# 06_PFI_Buffer.net
KiCad netlist of a schematic drawn in Altium Designer
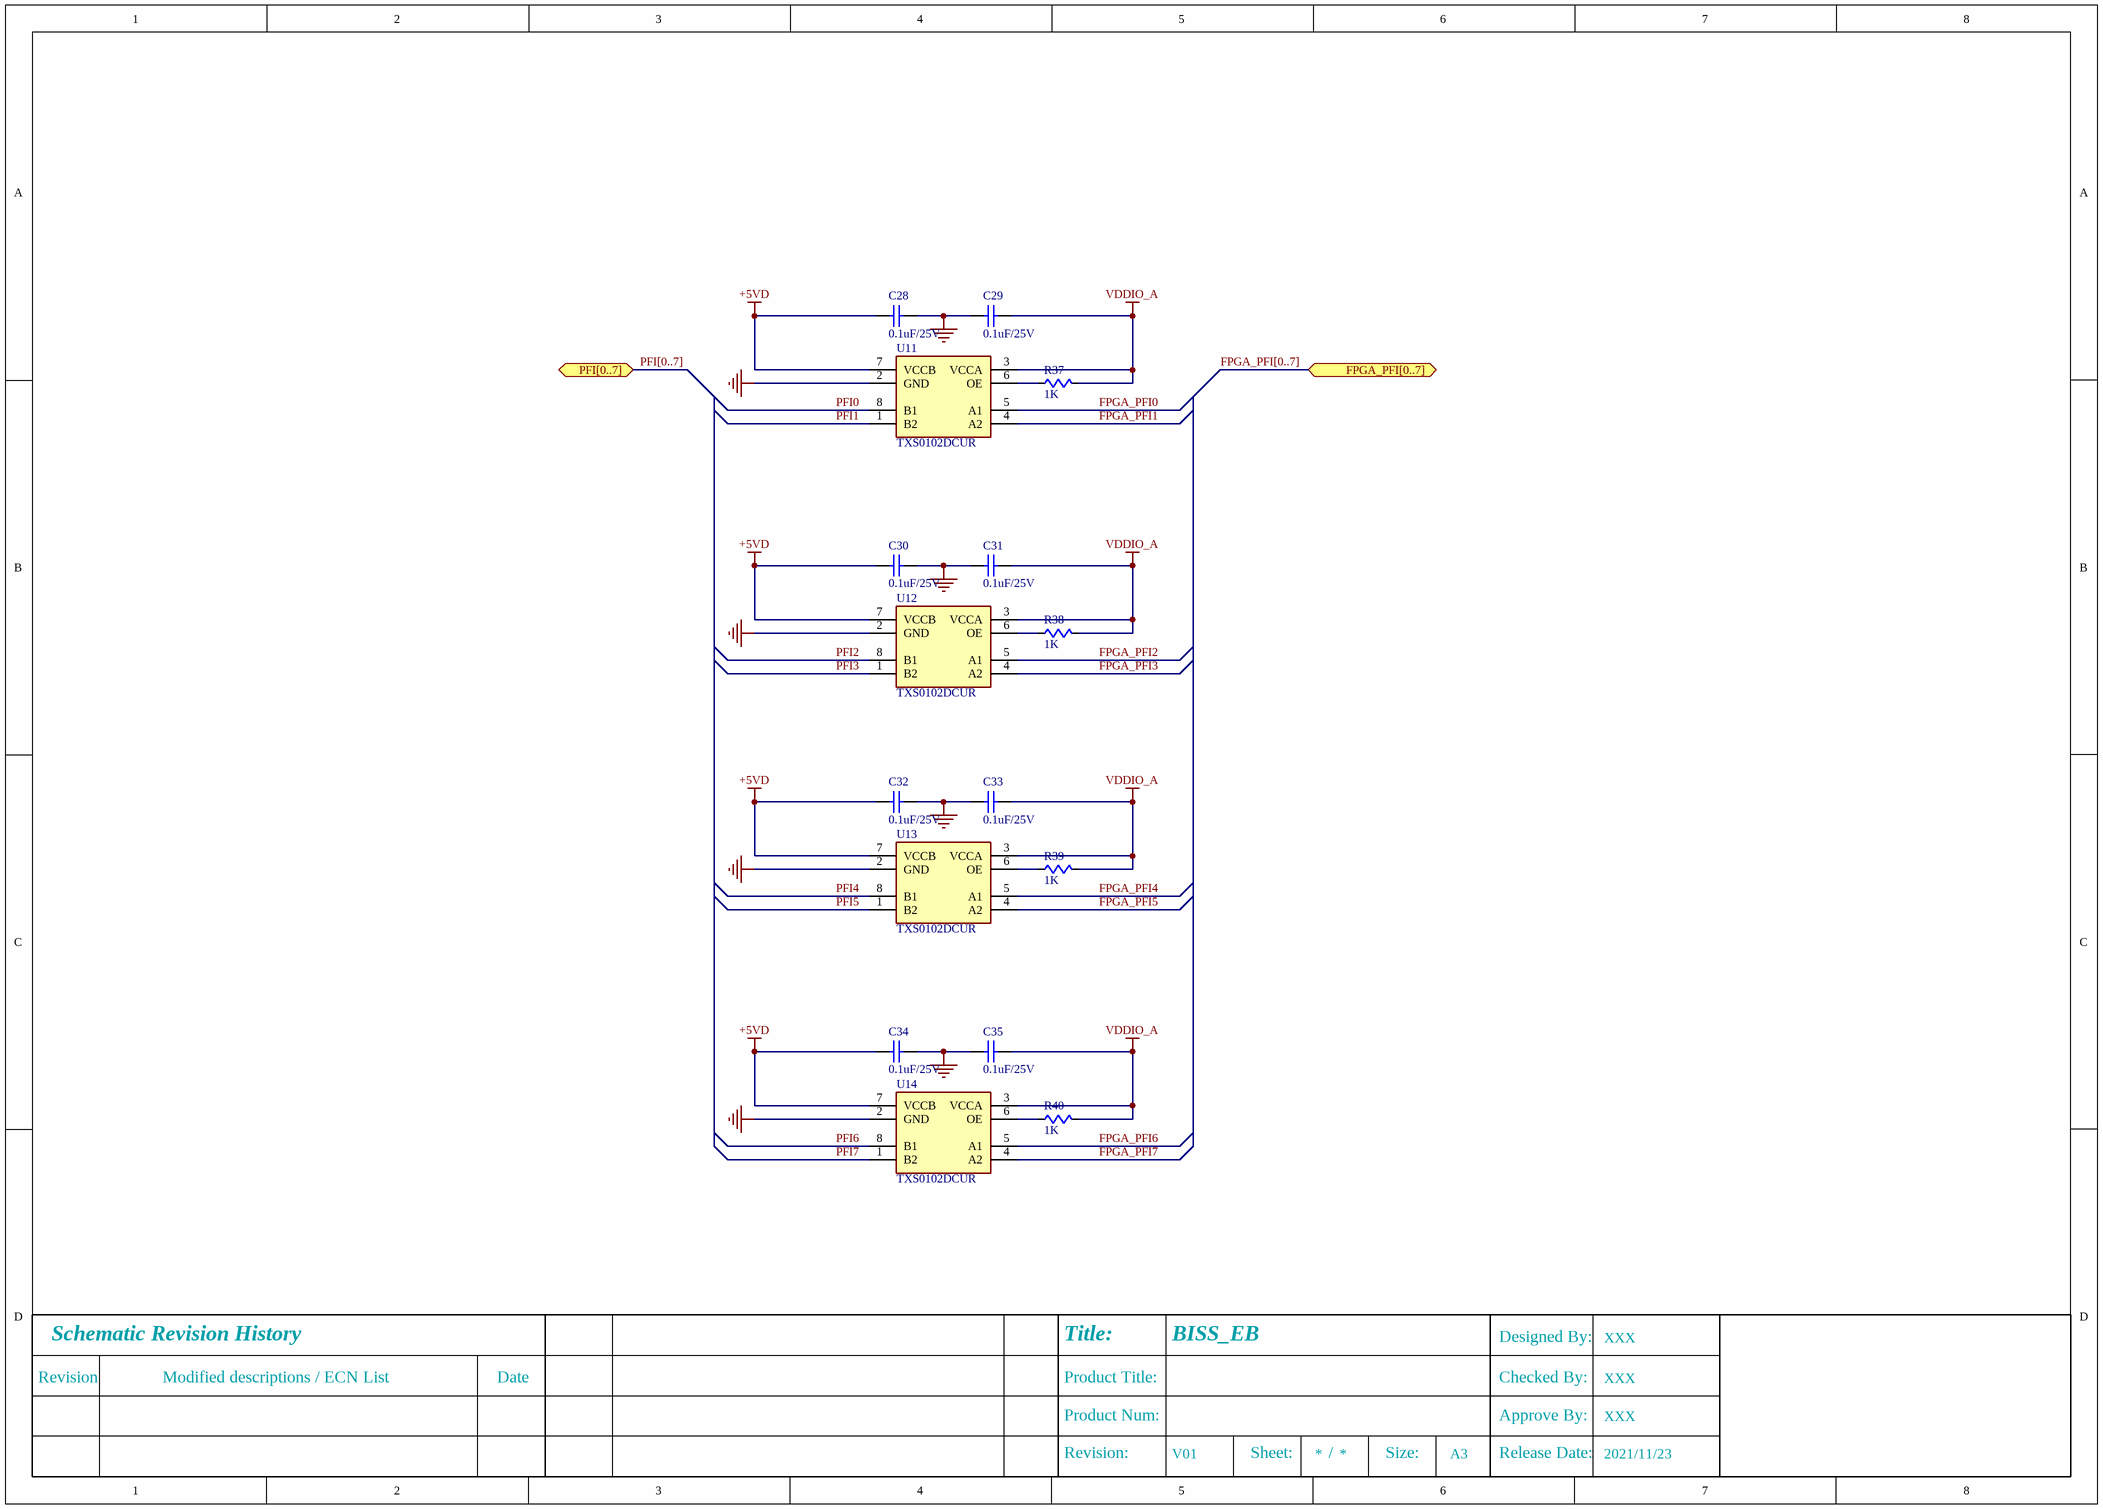
[diagram p0: 06_PFI_Buffer.SchDoc]

(export (version "E")
  (design (tool "Eeschema 10.0.6"))
  (components
    (comp (ref "C28")
      (value "0.1uF/25V")
      (footprint "C0603")
      (description "MLCC")
      (libsource (lib "SamacSys") (part "C"))
    )
    (comp (ref "C29")
      (value "0.1uF/25V")
      (footprint "C0603")
      (description "MLCC")
      (libsource (lib "SamacSys") (part "C"))
    )
    (comp (ref "C30")
      (value "0.1uF/25V")
      (footprint "C0603")
      (description "MLCC")
      (libsource (lib "SamacSys") (part "C"))
    )
    (comp (ref "C31")
      (value "0.1uF/25V")
      (footprint "C0603")
      (description "MLCC")
      (libsource (lib "SamacSys") (part "C"))
    )
    (comp (ref "C32")
      (value "0.1uF/25V")
      (footprint "C0603")
      (description "MLCC")
      (libsource (lib "SamacSys") (part "C"))
    )
    (comp (ref "C33")
      (value "0.1uF/25V")
      (footprint "C0603")
      (description "MLCC")
      (libsource (lib "SamacSys") (part "C"))
    )
    (comp (ref "C34")
      (value "0.1uF/25V")
      (footprint "C0603")
      (description "MLCC")
      (libsource (lib "SamacSys") (part "C"))
    )
    (comp (ref "C35")
      (value "0.1uF/25V")
      (footprint "C0603")
      (description "MLCC")
      (libsource (lib "SamacSys") (part "C"))
    )
    (comp (ref "R37")
      (value "1K")
      (footprint "SamacSys:R0603")
      (description "贴片电阻")
      (libsource (lib "SamacSys") (part "R"))
    )
    (comp (ref "R38")
      (value "1K")
      (footprint "SamacSys:R0603")
      (description "贴片电阻")
      (libsource (lib "SamacSys") (part "R"))
    )
    (comp (ref "R39")
      (value "1K")
      (footprint "SamacSys:R0603")
      (description "贴片电阻")
      (libsource (lib "SamacSys") (part "R"))
    )
    (comp (ref "R40")
      (value "1K")
      (footprint "SamacSys:R0603")
      (description "贴片电阻")
      (libsource (lib "SamacSys") (part "R"))
    )
    (comp (ref "U11")
      (value "TXS0102DCUR")
      (footprint "SamacSys:SOP50P310X90-8N")
      (description "Integrated Circuit")
      (fields (field (name "MOUSER PART NUMBER") "595-TXS0102DCUR"))
      (libsource (lib "SamacSys") (part "TXS0102DCUR"))
    )
    (comp (ref "U12")
      (value "TXS0102DCUR")
      (footprint "SamacSys:SOP50P310X90-8N")
      (description "Integrated Circuit")
      (fields (field (name "MOUSER PART NUMBER") "595-TXS0102DCUR"))
      (libsource (lib "SamacSys") (part "TXS0102DCUR"))
    )
    (comp (ref "U13")
      (value "TXS0102DCUR")
      (footprint "SamacSys:SOP50P310X90-8N")
      (description "Integrated Circuit")
      (fields (field (name "MOUSER PART NUMBER") "595-TXS0102DCUR"))
      (libsource (lib "SamacSys") (part "TXS0102DCUR"))
    )
    (comp (ref "U14")
      (value "TXS0102DCUR")
      (footprint "SamacSys:SOP50P310X90-8N")
      (description "Integrated Circuit")
      (fields (field (name "MOUSER PART NUMBER") "595-TXS0102DCUR"))
      (libsource (lib "SamacSys") (part "TXS0102DCUR"))
    )
  )
  (nets
    (net (code "1") (name "+5VD") (class "Default")
      (node (ref "C28") (pin "1") (pinfunction "1_1") (pintype "passive"))
      (node (ref "C30") (pin "1") (pinfunction "1_1") (pintype "passive"))
      (node (ref "C32") (pin "1") (pinfunction "1_1") (pintype "passive"))
      (node (ref "C34") (pin "1") (pinfunction "1_1") (pintype "passive"))
      (node (ref "U11") (pin "7") (pinfunction "VCCB_7") (pintype "passive"))
      (node (ref "U12") (pin "7") (pinfunction "VCCB_7") (pintype "passive"))
      (node (ref "U13") (pin "7") (pinfunction "VCCB_7") (pintype "passive"))
      (node (ref "U14") (pin "7") (pinfunction "VCCB_7") (pintype "passive"))
    )
    (net (code "2") (name "/FPGA_PFI0") (class "Default")
      (node (ref "U11") (pin "5") (pinfunction "A1_5") (pintype "passive"))
    )
    (net (code "3") (name "/FPGA_PFI1") (class "Default")
      (node (ref "U11") (pin "4") (pinfunction "A2_4") (pintype "passive"))
    )
    (net (code "4") (name "/FPGA_PFI2") (class "Default")
      (node (ref "U12") (pin "5") (pinfunction "A1_5") (pintype "passive"))
    )
    (net (code "5") (name "/FPGA_PFI3") (class "Default")
      (node (ref "U12") (pin "4") (pinfunction "A2_4") (pintype "passive"))
    )
    (net (code "6") (name "/FPGA_PFI4") (class "Default")
      (node (ref "U13") (pin "5") (pinfunction "A1_5") (pintype "passive"))
    )
    (net (code "7") (name "/FPGA_PFI5") (class "Default")
      (node (ref "U13") (pin "4") (pinfunction "A2_4") (pintype "passive"))
    )
    (net (code "8") (name "/FPGA_PFI6") (class "Default")
      (node (ref "U14") (pin "5") (pinfunction "A1_5") (pintype "passive"))
    )
    (net (code "9") (name "/FPGA_PFI7") (class "Default")
      (node (ref "U14") (pin "4") (pinfunction "A2_4") (pintype "passive"))
    )
    (net (code "11") (name "/PFI0") (class "Default")
      (node (ref "U11") (pin "8") (pinfunction "B1_8") (pintype "passive"))
    )
    (net (code "12") (name "/PFI1") (class "Default")
      (node (ref "U11") (pin "1") (pinfunction "B2_1") (pintype "passive"))
    )
    (net (code "13") (name "/PFI2") (class "Default")
      (node (ref "U12") (pin "8") (pinfunction "B1_8") (pintype "passive"))
    )
    (net (code "14") (name "/PFI3") (class "Default")
      (node (ref "U12") (pin "1") (pinfunction "B2_1") (pintype "passive"))
    )
    (net (code "15") (name "/PFI4") (class "Default")
      (node (ref "U13") (pin "8") (pinfunction "B1_8") (pintype "passive"))
    )
    (net (code "16") (name "/PFI5") (class "Default")
      (node (ref "U13") (pin "1") (pinfunction "B2_1") (pintype "passive"))
    )
    (net (code "17") (name "/PFI6") (class "Default")
      (node (ref "U14") (pin "8") (pinfunction "B1_8") (pintype "passive"))
    )
    (net (code "18") (name "/PFI7") (class "Default")
      (node (ref "U14") (pin "1") (pinfunction "B2_1") (pintype "passive"))
    )
    (net (code "20") (name "GND") (class "Default")
      (node (ref "C28") (pin "2") (pinfunction "2_2") (pintype "passive"))
      (node (ref "C29") (pin "1") (pinfunction "1_1") (pintype "passive"))
      (node (ref "C30") (pin "2") (pinfunction "2_2") (pintype "passive"))
      (node (ref "C31") (pin "1") (pinfunction "1_1") (pintype "passive"))
      (node (ref "C32") (pin "2") (pinfunction "2_2") (pintype "passive"))
      (node (ref "C33") (pin "1") (pinfunction "1_1") (pintype "passive"))
      (node (ref "C34") (pin "2") (pinfunction "2_2") (pintype "passive"))
      (node (ref "C35") (pin "1") (pinfunction "1_1") (pintype "passive"))
      (node (ref "U11") (pin "2") (pinfunction "GND_2") (pintype "passive"))
      (node (ref "U12") (pin "2") (pinfunction "GND_2") (pintype "passive"))
      (node (ref "U13") (pin "2") (pinfunction "GND_2") (pintype "passive"))
      (node (ref "U14") (pin "2") (pinfunction "GND_2") (pintype "passive"))
    )
    (net (code "21") (name "Net-(U11-OE)") (class "Default")
      (node (ref "R37") (pin "1") (pinfunction "1_1") (pintype "passive"))
      (node (ref "U11") (pin "6") (pinfunction "OE_6") (pintype "passive"))
    )
    (net (code "22") (name "Net-(U12-OE)") (class "Default")
      (node (ref "R38") (pin "1") (pinfunction "1_1") (pintype "passive"))
      (node (ref "U12") (pin "6") (pinfunction "OE_6") (pintype "passive"))
    )
    (net (code "23") (name "Net-(U13-OE)") (class "Default")
      (node (ref "R39") (pin "1") (pinfunction "1_1") (pintype "passive"))
      (node (ref "U13") (pin "6") (pinfunction "OE_6") (pintype "passive"))
    )
    (net (code "24") (name "Net-(U14-OE)") (class "Default")
      (node (ref "R40") (pin "1") (pinfunction "1_1") (pintype "passive"))
      (node (ref "U14") (pin "6") (pinfunction "OE_6") (pintype "passive"))
    )
    (net (code "25") (name "VDDIO_A") (class "Default")
      (node (ref "C29") (pin "2") (pinfunction "2_2") (pintype "passive"))
      (node (ref "C31") (pin "2") (pinfunction "2_2") (pintype "passive"))
      (node (ref "C33") (pin "2") (pinfunction "2_2") (pintype "passive"))
      (node (ref "C35") (pin "2") (pinfunction "2_2") (pintype "passive"))
      (node (ref "R37") (pin "2") (pinfunction "2_2") (pintype "passive"))
      (node (ref "R38") (pin "2") (pinfunction "2_2") (pintype "passive"))
      (node (ref "R39") (pin "2") (pinfunction "2_2") (pintype "passive"))
      (node (ref "R40") (pin "2") (pinfunction "2_2") (pintype "passive"))
      (node (ref "U11") (pin "3") (pinfunction "VCCA_3") (pintype "passive"))
      (node (ref "U12") (pin "3") (pinfunction "VCCA_3") (pintype "passive"))
      (node (ref "U13") (pin "3") (pinfunction "VCCA_3") (pintype "passive"))
      (node (ref "U14") (pin "3") (pinfunction "VCCA_3") (pintype "passive"))
    )
  )
)
